# STM32.net
KiCad netlist of a schematic drawn in Altium Designer
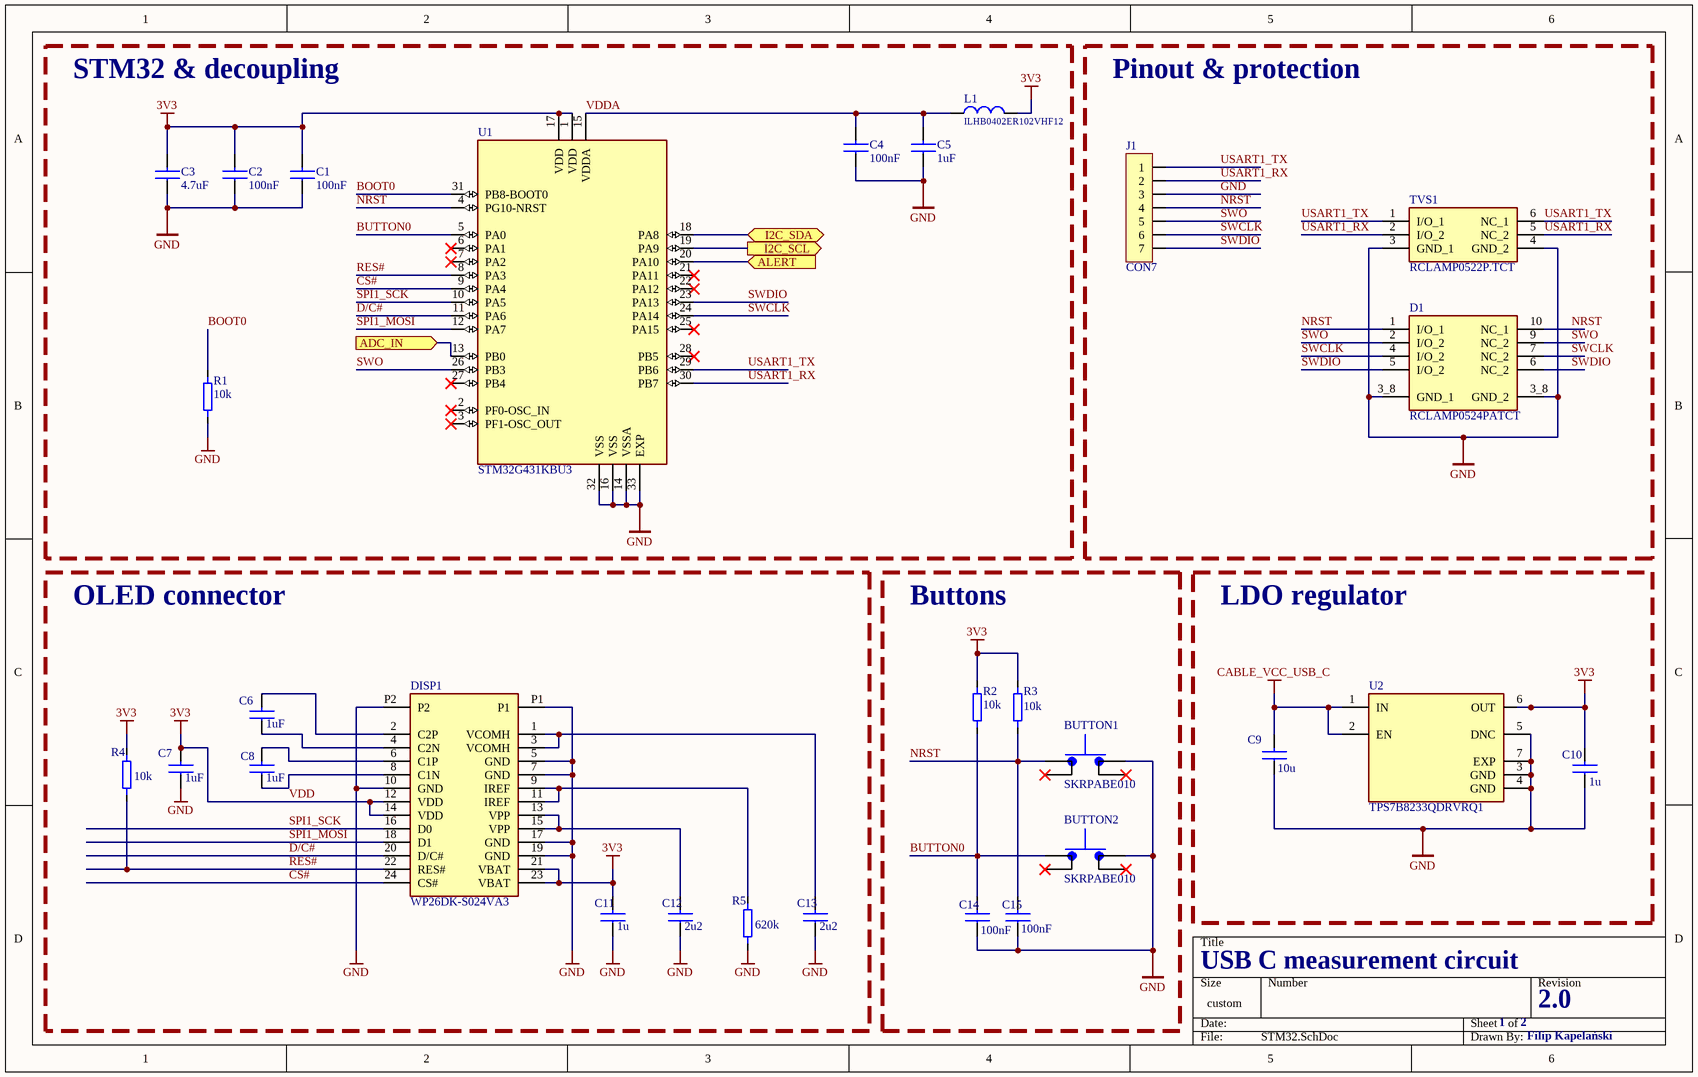
[diagram p0: STM32.SchDoc]

(export (version "E")
  (design (tool "Eeschema 10.0.6"))
  (components
    (comp (ref "BUTTON1")
      (value "SKRPABE010")
      (footprint "SKRPABE010")
      (description "Switch Tactile N.O. SPST Button J-Bend 0.05A 16VDC 1.57N SMD Automotive T/R")
      (libsource (lib "Switche") (part "SKRPABE010"))
    )
    (comp (ref "BUTTON2")
      (value "SKRPABE010")
      (footprint "SKRPABE010")
      (description "Switch Tactile N.O. SPST Button J-Bend 0.05A 16VDC 1.57N SMD Automotive T/R")
      (libsource (lib "Switche") (part "SKRPABE010"))
    )
    (comp (ref "C1")
      (value "100nF")
      (footprint "C0402")
      (description "Kondensator ceramiczny SMD")
      (libsource (lib "n16_discrete") (part "C"))
    )
    (comp (ref "C2")
      (value "100nF")
      (footprint "C0402")
      (description "Kondensator ceramiczny SMD")
      (libsource (lib "n16_discrete") (part "C"))
    )
    (comp (ref "C3")
      (value "4.7uF")
      (footprint "C0402")
      (description "Kondensator ceramiczny SMD")
      (libsource (lib "n16_discrete") (part "C"))
    )
    (comp (ref "C4")
      (value "100nF")
      (footprint "C0402")
      (description "Kondensator ceramiczny SMD")
      (libsource (lib "n16_discrete") (part "C"))
    )
    (comp (ref "C5")
      (value "1uF")
      (footprint "C0402")
      (description "Kondensator ceramiczny SMD")
      (libsource (lib "n16_discrete") (part "C"))
    )
    (comp (ref "C6")
      (value "1uF")
      (footprint "C0402")
      (description "Kondensator ceramiczny SMD")
      (libsource (lib "n16_discrete") (part "C"))
    )
    (comp (ref "C7")
      (value "1uF")
      (footprint "C0402")
      (description "Kondensator ceramiczny SMD")
      (libsource (lib "n16_discrete") (part "C"))
    )
    (comp (ref "C8")
      (value "1uF")
      (footprint "C0402")
      (description "Kondensator ceramiczny SMD")
      (libsource (lib "n16_discrete") (part "C"))
    )
    (comp (ref "C9")
      (value "10u")
      (footprint "C0402")
      (description "Kondensator ceramiczny SMD")
      (libsource (lib "n16_discrete") (part "C"))
    )
    (comp (ref "C10")
      (value "1u")
      (footprint "C0402")
      (description "Kondensator ceramiczny SMD")
      (libsource (lib "n16_discrete") (part "C"))
    )
    (comp (ref "C11")
      (value "1u")
      (footprint "C0402")
      (description "Kondensator ceramiczny SMD")
      (libsource (lib "n16_discrete") (part "C"))
    )
    (comp (ref "C12")
      (value "2u2")
      (footprint "C0402")
      (description "Kondensator ceramiczny SMD")
      (libsource (lib "n16_discrete") (part "C"))
    )
    (comp (ref "C13")
      (value "2u2")
      (footprint "C0402")
      (description "Kondensator ceramiczny SMD")
      (libsource (lib "n16_discrete") (part "C"))
    )
    (comp (ref "C14")
      (value "100nF")
      (footprint "C0402")
      (description "Kondensator ceramiczny SMD")
      (libsource (lib "n16_discrete") (part "C"))
    )
    (comp (ref "C15")
      (value "100nF")
      (footprint "C0402")
      (description "Kondensator ceramiczny SMD")
      (libsource (lib "n16_discrete") (part "C"))
    )
    (comp (ref "D1")
      (value "RCLAMP0524PATCT")
      (footprint "DIO_RCLAMP0524PATCT")
      (description "15V Clamp 5A (8/20Âµs) Ipp Tvs Diode Surface Mount SLP2510P8")
      (fields (field (name "MF") "Semtech Corporation"))
      (libsource (lib "MyLibs") (part "RCLAMP0524PATCT"))
    )
    (comp (ref "DISP1")
      (value "WP26DK-S024VA3")
      (footprint "WP26DK-S024VA3")
      (libsource (lib "Optoelectronics") (part "WP26DK-S024VA3"))
    )
    (comp (ref "J1")
      (value "CON7")
      (footprint "SIP7")
      (description "Connector")
      (libsource (lib "n16_connector") (part "CON7"))
    )
    (comp (ref "L1")
      (value "ILHB0402ER102VHF12")
      (footprint "L0402")
      (description "Cewka/Koralik ferrytowy")
      (libsource (lib "n16_discrete") (part "L"))
    )
    (comp (ref "R1")
      (value "10k")
      (footprint "R0402")
      (description "Rezystor SMD")
      (libsource (lib "uEproject23") (part "R"))
    )
    (comp (ref "R2")
      (value "10k")
      (footprint "R0402")
      (description "Rezystor SMD")
      (libsource (lib "n16_discrete") (part "R"))
    )
    (comp (ref "R3")
      (value "10k")
      (footprint "R0402")
      (description "Rezystor SMD")
      (libsource (lib "n16_discrete") (part "R"))
    )
    (comp (ref "R4")
      (value "10k")
      (footprint "R0402")
      (description "Rezystor SMD")
      (libsource (lib "n16_discrete") (part "R"))
    )
    (comp (ref "R5")
      (value "620k")
      (footprint "R0402")
      (description "Rezystor SMD")
      (libsource (lib "n16_discrete") (part "R"))
    )
    (comp (ref "TVS1")
      (value "RCLAMP0522P.TCT")
      (footprint "RCLAMP0522PTCT")
      (description "TVS Diode (Bi-directional)")
      (fields (field (name "MOUSER PART NUMBER") "947-RCLAMP0522P.TCT"))
      (libsource (lib "MyLibs") (part "RCLAMP0522P.TCT"))
    )
    (comp (ref "U1")
      (value "STM32G431KBU3")
      (footprint "STM32G431KBU3")
      (libsource (lib "STM32") (part "STM32G431KBU3"))
    )
    (comp (ref "U2")
      (value "TPS7B8233QDRVRQ1")
      (footprint "TPS7B8233QDRVRQ1")
      (libsource (lib "LDO") (part "TPS7B8233QDRVRQ1"))
    )
  )
  (nets
    (net (code "1") (name "/ADC_IN") (class "Default")
      (node (ref "U1") (pin "13") (pinfunction "PB0_13") (pintype "bidirectional"))
    )
    (net (code "2") (name "/ALERT") (class "Default")
      (node (ref "U1") (pin "20") (pinfunction "PA10_20") (pintype "bidirectional"))
    )
    (net (code "3") (name "/BOOT0") (class "Default")
      (node (ref "R1") (pin "2") (pinfunction "2_2") (pintype "passive"))
      (node (ref "U1") (pin "31") (pinfunction "PB8-BOOT0_31") (pintype "bidirectional"))
    )
    (net (code "4") (name "/BUTTON0") (class "Default")
      (node (ref "BUTTON2") (pin "1") (pinfunction "1_1") (pintype "passive"))
      (node (ref "C14") (pin "2") (pinfunction "2_2") (pintype "passive"))
      (node (ref "R2") (pin "2") (pinfunction "2_2") (pintype "passive"))
      (node (ref "U1") (pin "5") (pinfunction "PA0_5") (pintype "bidirectional"))
    )
    (net (code "5") (name "/CS#") (class "Default")
      (node (ref "DISP1") (pin "24") (pinfunction "CS#_24") (pintype "passive"))
      (node (ref "U1") (pin "9") (pinfunction "PA4_9") (pintype "bidirectional"))
    )
    (net (code "6") (name "/D{slash}C#") (class "Default")
      (node (ref "DISP1") (pin "20") (pinfunction "D/C#_20") (pintype "passive"))
      (node (ref "U1") (pin "11") (pinfunction "PA6_11") (pintype "bidirectional"))
    )
    (net (code "7") (name "/I2C_SCL") (class "Default")
      (node (ref "U1") (pin "19") (pinfunction "PA9_19") (pintype "bidirectional"))
    )
    (net (code "8") (name "/I2C_SDA") (class "Default")
      (node (ref "U1") (pin "18") (pinfunction "PA8_18") (pintype "bidirectional"))
    )
    (net (code "9") (name "/NRST") (class "Default")
      (node (ref "BUTTON1") (pin "1") (pinfunction "1_1") (pintype "passive"))
      (node (ref "C15") (pin "2") (pinfunction "2_2") (pintype "passive"))
      (node (ref "D1") (pin "1") (pinfunction "I/O_1_1") (pintype "passive"))
      (node (ref "D1") (pin "10") (pinfunction "NC_1_10") (pintype "passive"))
      (node (ref "J1") (pin "4") (pinfunction "4_4") (pintype "passive"))
      (node (ref "R3") (pin "2") (pinfunction "2_2") (pintype "passive"))
      (node (ref "U1") (pin "4") (pinfunction "PG10-NRST_4") (pintype "bidirectional"))
    )
    (net (code "10") (name "/RES#") (class "Default")
      (node (ref "DISP1") (pin "22") (pinfunction "RES#_22") (pintype "passive"))
      (node (ref "R4") (pin "2") (pinfunction "2_2") (pintype "passive"))
      (node (ref "U1") (pin "8") (pinfunction "PA3_8") (pintype "bidirectional"))
    )
    (net (code "11") (name "/SPI1_MOSI") (class "Default")
      (node (ref "DISP1") (pin "18") (pinfunction "D1_18") (pintype "passive"))
      (node (ref "U1") (pin "12") (pinfunction "PA7_12") (pintype "bidirectional"))
    )
    (net (code "12") (name "/SPI1_SCK") (class "Default")
      (node (ref "DISP1") (pin "16") (pinfunction "D0_16") (pintype "passive"))
      (node (ref "U1") (pin "10") (pinfunction "PA5_10") (pintype "bidirectional"))
    )
    (net (code "13") (name "/SWCLK") (class "Default")
      (node (ref "D1") (pin "4") (pinfunction "I/O_2_4") (pintype "passive"))
      (node (ref "D1") (pin "7") (pinfunction "NC_2_7") (pintype "passive"))
      (node (ref "J1") (pin "6") (pinfunction "6_6") (pintype "passive"))
      (node (ref "U1") (pin "24") (pinfunction "PA14_24") (pintype "bidirectional"))
    )
    (net (code "14") (name "/SWDIO") (class "Default")
      (node (ref "D1") (pin "5") (pinfunction "I/O_2_5") (pintype "passive"))
      (node (ref "D1") (pin "6") (pinfunction "NC_2_6") (pintype "passive"))
      (node (ref "J1") (pin "7") (pinfunction "7_7") (pintype "passive"))
      (node (ref "U1") (pin "23") (pinfunction "PA13_23") (pintype "bidirectional"))
    )
    (net (code "15") (name "/SWO") (class "Default")
      (node (ref "D1") (pin "2") (pinfunction "I/O_2_2") (pintype "passive"))
      (node (ref "D1") (pin "9") (pinfunction "NC_2_9") (pintype "passive"))
      (node (ref "J1") (pin "5") (pinfunction "5_5") (pintype "passive"))
      (node (ref "U1") (pin "26") (pinfunction "PB3_26") (pintype "bidirectional"))
    )
    (net (code "16") (name "/USART1_RX") (class "Default")
      (node (ref "J1") (pin "2") (pinfunction "2_2") (pintype "passive"))
      (node (ref "TVS1") (pin "2") (pinfunction "I/O_2_2") (pintype "passive"))
      (node (ref "TVS1") (pin "5") (pinfunction "NC_2_5") (pintype "passive"))
      (node (ref "U1") (pin "30") (pinfunction "PB7_30") (pintype "bidirectional"))
    )
    (net (code "17") (name "/USART1_TX") (class "Default")
      (node (ref "J1") (pin "1") (pinfunction "1_1") (pintype "passive"))
      (node (ref "TVS1") (pin "1") (pinfunction "I/O_1_1") (pintype "passive"))
      (node (ref "TVS1") (pin "6") (pinfunction "NC_1_6") (pintype "passive"))
      (node (ref "U1") (pin "29") (pinfunction "PB6_29") (pintype "bidirectional"))
    )
    (net (code "18") (name "/VDDA") (class "Default")
      (node (ref "C4") (pin "2") (pinfunction "2_2") (pintype "passive"))
      (node (ref "C5") (pin "2") (pinfunction "2_2") (pintype "passive"))
      (node (ref "L1") (pin "2") (pinfunction "2_2") (pintype "passive"))
      (node (ref "U1") (pin "15") (pinfunction "VDDA_15") (pintype "power_in"))
    )
    (net (code "19") (name "3V3") (class "Default")
      (node (ref "C1") (pin "2") (pinfunction "2_2") (pintype "passive"))
      (node (ref "C10") (pin "2") (pinfunction "2_2") (pintype "passive"))
      (node (ref "C11") (pin "2") (pinfunction "2_2") (pintype "passive"))
      (node (ref "C2") (pin "2") (pinfunction "2_2") (pintype "passive"))
      (node (ref "C3") (pin "2") (pinfunction "2_2") (pintype "passive"))
      (node (ref "C7") (pin "2") (pinfunction "2_2") (pintype "passive"))
      (node (ref "DISP1") (pin "12") (pinfunction "VDD_12") (pintype "passive"))
      (node (ref "DISP1") (pin "14") (pinfunction "VDD_14") (pintype "passive"))
      (node (ref "DISP1") (pin "21") (pinfunction "VBAT_21") (pintype "passive"))
      (node (ref "DISP1") (pin "23") (pinfunction "VBAT_23") (pintype "passive"))
      (node (ref "L1") (pin "1") (pinfunction "1_1") (pintype "passive"))
      (node (ref "R2") (pin "1") (pinfunction "1_1") (pintype "passive"))
      (node (ref "R3") (pin "1") (pinfunction "1_1") (pintype "passive"))
      (node (ref "R4") (pin "1") (pinfunction "1_1") (pintype "passive"))
      (node (ref "U1") (pin "1") (pinfunction "VDD_1") (pintype "power_in"))
      (node (ref "U1") (pin "17") (pinfunction "VDD_17") (pintype "power_in"))
      (node (ref "U2") (pin "6") (pinfunction "OUT_6") (pintype "power_in"))
    )
    (net (code "20") (name "CABLE_VCC_USB_C") (class "Default")
      (node (ref "C9") (pin "2") (pinfunction "2_2") (pintype "passive"))
      (node (ref "U2") (pin "1") (pinfunction "IN_1") (pintype "power_in"))
      (node (ref "U2") (pin "2") (pinfunction "EN_2") (pintype "power_in"))
    )
    (net (code "21") (name "GND") (class "Default")
      (node (ref "BUTTON1") (pin "3") (pinfunction "2_3") (pintype "passive"))
      (node (ref "BUTTON2") (pin "3") (pinfunction "2_3") (pintype "passive"))
      (node (ref "C1") (pin "1") (pinfunction "1_1") (pintype "passive"))
      (node (ref "C10") (pin "1") (pinfunction "1_1") (pintype "passive"))
      (node (ref "C11") (pin "1") (pinfunction "1_1") (pintype "passive"))
      (node (ref "C12") (pin "1") (pinfunction "1_1") (pintype "passive"))
      (node (ref "C13") (pin "1") (pinfunction "1_1") (pintype "passive"))
      (node (ref "C14") (pin "1") (pinfunction "1_1") (pintype "passive"))
      (node (ref "C15") (pin "1") (pinfunction "1_1") (pintype "passive"))
      (node (ref "C2") (pin "1") (pinfunction "1_1") (pintype "passive"))
      (node (ref "C3") (pin "1") (pinfunction "1_1") (pintype "passive"))
      (node (ref "C4") (pin "1") (pinfunction "1_1") (pintype "passive"))
      (node (ref "C5") (pin "1") (pinfunction "1_1") (pintype "passive"))
      (node (ref "C7") (pin "1") (pinfunction "1_1") (pintype "passive"))
      (node (ref "C9") (pin "1") (pinfunction "1_1") (pintype "passive"))
      (node (ref "D1") (pin "3_8") (pinfunction "GND_1_3_8") (pintype "passive"))
      (node (ref "DISP1") (pin "10") (pinfunction "GND_10") (pintype "passive"))
      (node (ref "DISP1") (pin "17") (pinfunction "GND_17") (pintype "passive"))
      (node (ref "DISP1") (pin "19") (pinfunction "GND_19") (pintype "passive"))
      (node (ref "DISP1") (pin "5") (pinfunction "GND_5") (pintype "passive"))
      (node (ref "DISP1") (pin "7") (pinfunction "GND_7") (pintype "passive"))
      (node (ref "DISP1") (pin "P1") (pinfunction "P1_P1") (pintype "power_in"))
      (node (ref "DISP1") (pin "P2") (pinfunction "P2_P2") (pintype "power_in"))
      (node (ref "J1") (pin "3") (pinfunction "3_3") (pintype "passive"))
      (node (ref "R1") (pin "1") (pinfunction "1_1") (pintype "passive"))
      (node (ref "R5") (pin "2") (pinfunction "2_2") (pintype "passive"))
      (node (ref "TVS1") (pin "3") (pinfunction "GND_1_3") (pintype "passive"))
      (node (ref "TVS1") (pin "4") (pinfunction "GND_2_4") (pintype "passive"))
      (node (ref "U1") (pin "14") (pinfunction "VSSA_14") (pintype "power_in"))
      (node (ref "U1") (pin "16") (pinfunction "VSS_16") (pintype "power_in"))
      (node (ref "U1") (pin "32") (pinfunction "VSS_32") (pintype "power_in"))
      (node (ref "U1") (pin "33") (pinfunction "EXP_33") (pintype "power_in"))
      (node (ref "U2") (pin "3") (pinfunction "GND_3") (pintype "power_in"))
      (node (ref "U2") (pin "4") (pinfunction "GND_4") (pintype "power_in"))
      (node (ref "U2") (pin "5") (pinfunction "DNC_5") (pintype "passive"))
      (node (ref "U2") (pin "7") (pinfunction "EXP_7") (pintype "power_in"))
    )
    (net (code "22") (name "Net-(C12-Pad2)") (class "Default")
      (node (ref "C12") (pin "2") (pinfunction "2_2") (pintype "passive"))
      (node (ref "DISP1") (pin "13") (pinfunction "VPP_13") (pintype "passive"))
      (node (ref "DISP1") (pin "15") (pinfunction "VPP_15") (pintype "passive"))
    )
    (net (code "23") (name "Net-(C13-Pad2)") (class "Default")
      (node (ref "C13") (pin "2") (pinfunction "2_2") (pintype "passive"))
      (node (ref "DISP1") (pin "1") (pinfunction "VCOMH_1") (pintype "passive"))
      (node (ref "DISP1") (pin "3") (pinfunction "VCOMH_3") (pintype "passive"))
    )
    (net (code "24") (name "Net-(DISP1-C1N)") (class "Default")
      (node (ref "C8") (pin "1") (pinfunction "1_1") (pintype "passive"))
      (node (ref "DISP1") (pin "8") (pinfunction "C1N_8") (pintype "passive"))
    )
    (net (code "25") (name "Net-(DISP1-C1P)") (class "Default")
      (node (ref "C8") (pin "2") (pinfunction "2_2") (pintype "passive"))
      (node (ref "DISP1") (pin "6") (pinfunction "C1P_6") (pintype "passive"))
    )
    (net (code "26") (name "Net-(DISP1-C2N)") (class "Default")
      (node (ref "C6") (pin "1") (pinfunction "1_1") (pintype "passive"))
      (node (ref "DISP1") (pin "4") (pinfunction "C2N_4") (pintype "passive"))
    )
    (net (code "27") (name "Net-(DISP1-C2P)") (class "Default")
      (node (ref "C6") (pin "2") (pinfunction "2_2") (pintype "passive"))
      (node (ref "DISP1") (pin "2") (pinfunction "C2P_2") (pintype "passive"))
    )
    (net (code "28") (name "Net-(DISP1-IREF-Pad11)") (class "Default")
      (node (ref "DISP1") (pin "11") (pinfunction "IREF_11") (pintype "passive"))
      (node (ref "DISP1") (pin "9") (pinfunction "IREF_9") (pintype "passive"))
      (node (ref "R5") (pin "1") (pinfunction "1_1") (pintype "passive"))
    )
    (net (code "29") (name "unconnected-(BUTTON1-1-Pad2)") (class "Default")
      (node (ref "BUTTON1") (pin "2") (pinfunction "1_2") (pintype "passive+no_connect"))
    )
    (net (code "30") (name "unconnected-(BUTTON1-2-Pad4)") (class "Default")
      (node (ref "BUTTON1") (pin "4") (pinfunction "2_4") (pintype "passive+no_connect"))
    )
    (net (code "31") (name "unconnected-(BUTTON2-1-Pad2)") (class "Default")
      (node (ref "BUTTON2") (pin "2") (pinfunction "1_2") (pintype "passive+no_connect"))
    )
    (net (code "32") (name "unconnected-(BUTTON2-2-Pad4)") (class "Default")
      (node (ref "BUTTON2") (pin "4") (pinfunction "2_4") (pintype "passive+no_connect"))
    )
    (net (code "33") (name "unconnected-(U1-PA1-Pad6)") (class "Default")
      (node (ref "U1") (pin "6") (pinfunction "PA1_6") (pintype "bidirectional+no_connect"))
    )
    (net (code "34") (name "unconnected-(U1-PA2-Pad7)") (class "Default")
      (node (ref "U1") (pin "7") (pinfunction "PA2_7") (pintype "bidirectional+no_connect"))
    )
    (net (code "35") (name "unconnected-(U1-PA11-Pad21)") (class "Default")
      (node (ref "U1") (pin "21") (pinfunction "PA11_21") (pintype "bidirectional+no_connect"))
    )
    (net (code "36") (name "unconnected-(U1-PA12-Pad22)") (class "Default")
      (node (ref "U1") (pin "22") (pinfunction "PA12_22") (pintype "bidirectional+no_connect"))
    )
    (net (code "37") (name "unconnected-(U1-PA15-Pad25)") (class "Default")
      (node (ref "U1") (pin "25") (pinfunction "PA15_25") (pintype "bidirectional+no_connect"))
    )
    (net (code "38") (name "unconnected-(U1-PB4-Pad27)") (class "Default")
      (node (ref "U1") (pin "27") (pinfunction "PB4_27") (pintype "bidirectional+no_connect"))
    )
    (net (code "39") (name "unconnected-(U1-PB5-Pad28)") (class "Default")
      (node (ref "U1") (pin "28") (pinfunction "PB5_28") (pintype "bidirectional+no_connect"))
    )
    (net (code "40") (name "unconnected-(U1-PF0-OSC_IN-Pad2)") (class "Default")
      (node (ref "U1") (pin "2") (pinfunction "PF0-OSC_IN_2") (pintype "bidirectional+no_connect"))
    )
    (net (code "41") (name "unconnected-(U1-PF1-OSC_OUT-Pad3)") (class "Default")
      (node (ref "U1") (pin "3") (pinfunction "PF1-OSC_OUT_3") (pintype "bidirectional+no_connect"))
    )
  )
)
